# MSB-PCB-1R1.net
KiCad netlist of a schematic drawn in Altium Designer
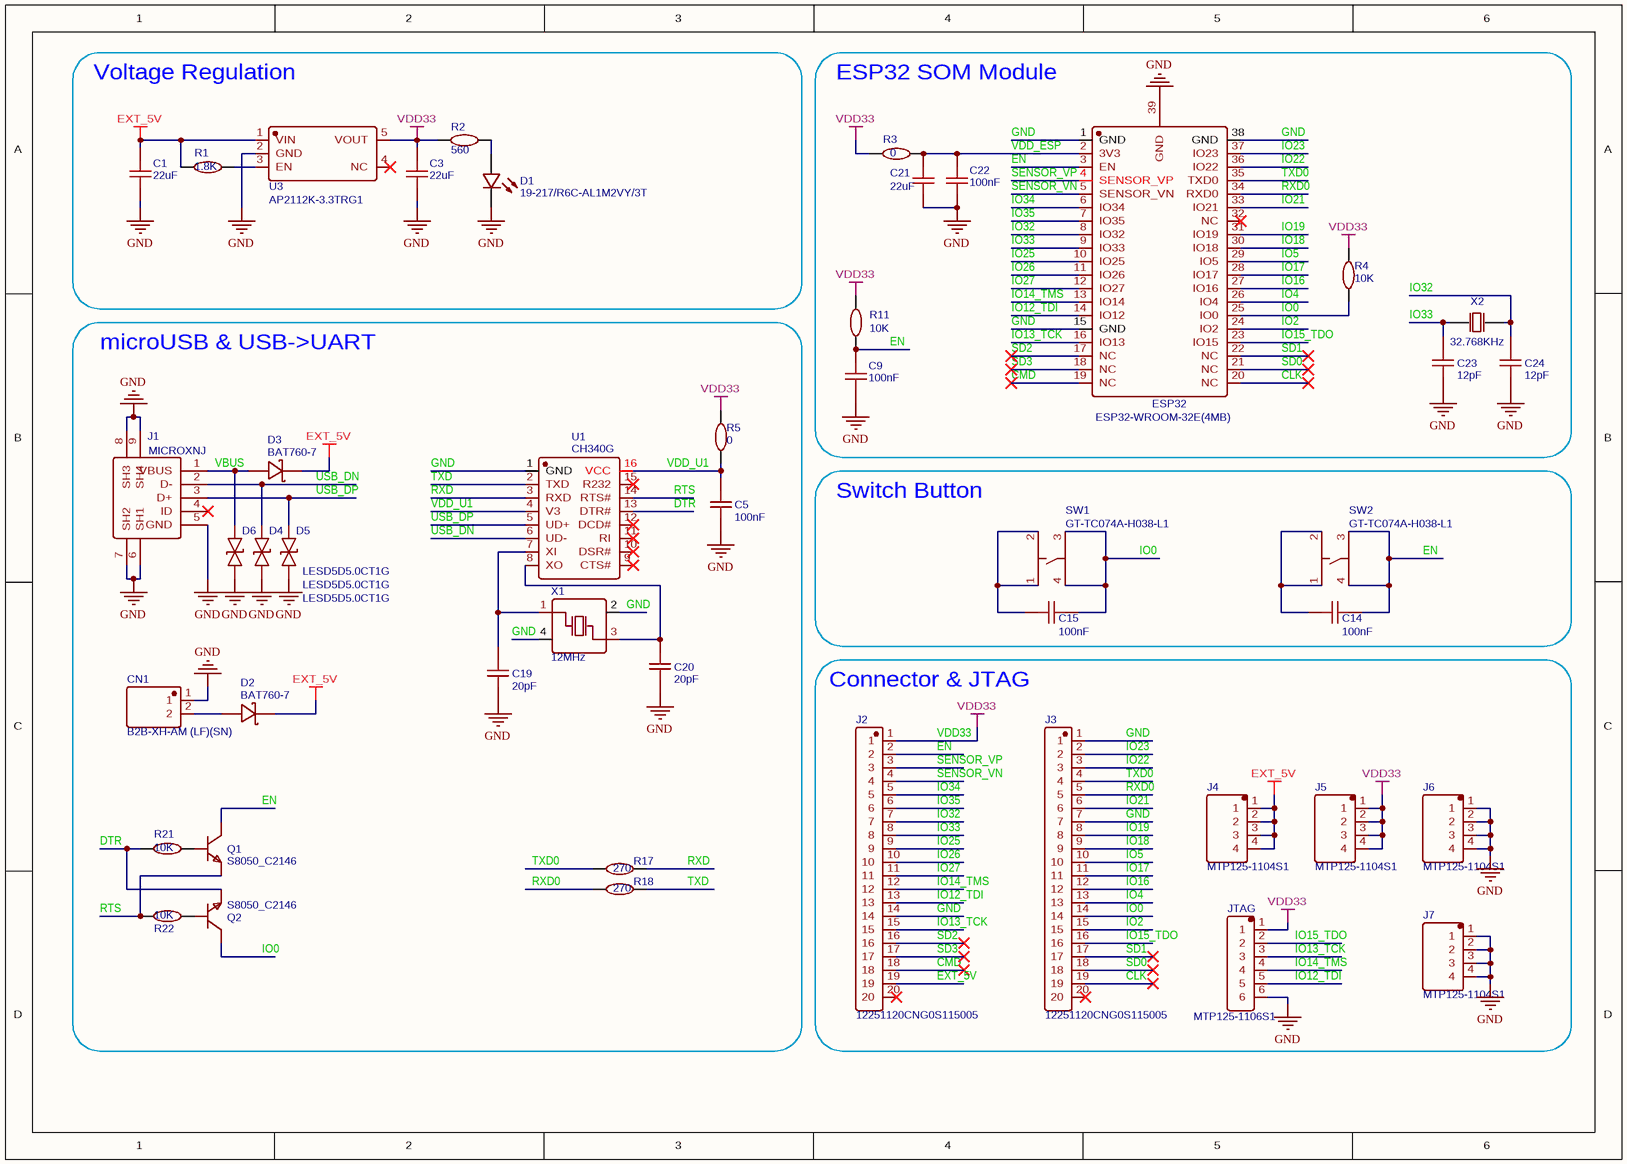
[diagram p0: MSB-PCB-1R1.schdoc]

(export (version "E")
  (design (tool "Eeschema 10.0.6"))
  (components
    (comp (ref "C1")
      (value "22uF")
      (footprint "C0603")
      (fields
        (field (name "BOM_SUPPLIER PART") "C167429")
        (field (name "BOM_MANUFACTURER PART") "GRM188R61A226ME15L")
        (field (name "CONTRIBUTOR") "LCSC")
      )
      (libsource (lib "altium-import") (part "root_1_22uF_"))
    )
    (comp (ref "C3")
      (value "22uF")
      (footprint "C0603")
      (fields
        (field (name "BOM_SUPPLIER PART") "C167429")
        (field (name "BOM_MANUFACTURER PART") "GRM188R61A226ME15L")
        (field (name "CONTRIBUTOR") "LCSC")
      )
      (libsource (lib "altium-import") (part "root_1_22uF_"))
    )
    (comp (ref "C5")
      (value "100nF")
      (footprint "C0603")
      (fields
        (field (name "BOM_MANUFACTURER PART") "CC0603KRX7R9BB104")
        (field (name "BOM_SUPPLIER PART") "C14663")
      )
      (libsource (lib "altium-import") (part "root_3_100nF_"))
    )
    (comp (ref "C9")
      (value "100nF")
      (footprint "C0603")
      (fields
        (field (name "BOM_MANUFACTURER PART") "CC0603KRX7R9BB104")
        (field (name "BOM_SUPPLIER PART") "C14663")
      )
      (libsource (lib "altium-import") (part "root_1_100nF_"))
    )
    (comp (ref "C14")
      (value "100nF")
      (footprint "C0603")
      (fields
        (field (name "BOM_MANUFACTURER PART") "CC0603KRX7R9BB104")
        (field (name "BOM_SUPPLIER PART") "C14663")
      )
      (libsource (lib "altium-import") (part "root_0_100nF_"))
    )
    (comp (ref "C15")
      (value "100nF")
      (footprint "C0603")
      (fields
        (field (name "BOM_MANUFACTURER PART") "CC0603KRX7R9BB104")
        (field (name "BOM_SUPPLIER PART") "C14663")
      )
      (libsource (lib "altium-import") (part "root_0_100nF_"))
    )
    (comp (ref "C19")
      (value "20pF")
      (footprint "C0603")
      (fields
        (field (name "BOM_SUPPLIER PART") "C376774")
        (field (name "BOM_MANUFACTURER PART") "TCC0603COG200J500CT")
        (field (name "CONTRIBUTOR") "LCSC")
      )
      (libsource (lib "altium-import") (part "root_0_20pF_"))
    )
    (comp (ref "C20")
      (value "20pF")
      (footprint "C0603")
      (fields
        (field (name "BOM_SUPPLIER PART") "C376774")
        (field (name "BOM_MANUFACTURER PART") "TCC0603COG200J500CT")
        (field (name "CONTRIBUTOR") "LCSC")
      )
      (libsource (lib "altium-import") (part "root_0_20pF_"))
    )
    (comp (ref "C21")
      (value "22uF")
      (footprint "C0603")
      (fields
        (field (name "BOM_SUPPLIER PART") "C167429")
        (field (name "BOM_MANUFACTURER PART") "GRM188R61A226ME15L")
        (field (name "CONTRIBUTOR") "LCSC")
      )
      (libsource (lib "altium-import") (part "root_1_22uF_"))
    )
    (comp (ref "C22")
      (value "100nF")
      (footprint "C0603")
      (fields
        (field (name "BOM_MANUFACTURER PART") "CC0603KRX7R9BB104")
        (field (name "BOM_SUPPLIER PART") "C14663")
      )
      (libsource (lib "altium-import") (part "root_1_100nF_"))
    )
    (comp (ref "C23")
      (value "12pF")
      (footprint "C0603")
      (fields
        (field (name "BOM_SUPPLIER PART") "C376767")
        (field (name "BOM_MANUFACTURER PART") "TCC0603COG120J500CT")
        (field (name "CONTRIBUTOR") "LCSC")
      )
      (libsource (lib "altium-import") (part "root_0_12pF_"))
    )
    (comp (ref "C24")
      (value "12pF")
      (footprint "C0603")
      (fields
        (field (name "BOM_SUPPLIER PART") "C376767")
        (field (name "BOM_MANUFACTURER PART") "TCC0603COG120J500CT")
        (field (name "CONTRIBUTOR") "LCSC")
      )
      (libsource (lib "altium-import") (part "root_0_12pF_"))
    )
    (comp (ref "CN1")
      (value "B2B-XH-AM (LF)(SN)")
      (footprint "CONN-TH_B2B-XH-AM-LF-SN")
      (fields (field (name "BOM_SUPPLIER PART") "C161869") (field (name "CONTRIBUTOR") "LCSC"))
      (libsource (lib "altium-import") (part "root_0_mirrored_B2B-XH-AM (LF)(SN)_"))
    )
    (comp (ref "D1")
      (value "19-217/R6C-AL1M2VY/3T")
      (footprint "LED0603-R-RD")
      (fields (field (name "BOM_SUPPLIER PART") "C72044"))
      (libsource (lib "altium-import") (part "root_3_19-217/R6C-AL1M2VY/3T_"))
    )
    (comp (ref "D2")
      (value "BAT760-7")
      (footprint "SOD-323_L1.8-W1.3-LS2.5-RD")
      (fields (field (name "BOM_SUPPLIER PART") "C124187") (field (name "CONTRIBUTOR") "LCSC"))
      (libsource (lib "altium-import") (part "root_2_BAT760-7_"))
    )
    (comp (ref "D3")
      (value "BAT760-7")
      (footprint "SOD-323_L1.8-W1.3-LS2.5-RD")
      (fields (field (name "BOM_SUPPLIER PART") "C124187") (field (name "CONTRIBUTOR") "LCSC"))
      (libsource (lib "altium-import") (part "root_2_BAT760-7_"))
    )
    (comp (ref "D4")
      (value "LESD5D5.0CT1G")
      (footprint "SOD-523_L1.2-W0.8-LS1.6-BI")
      (fields (field (name "BOM_SUPPLIER PART") "C383211") (field (name "CONTRIBUTOR") "LCSC"))
      (libsource (lib "altium-import") (part "root_1_LESD5D5.0CT1G_"))
    )
    (comp (ref "D5")
      (value "LESD5D5.0CT1G")
      (footprint "SOD-523_L1.2-W0.8-LS1.6-BI")
      (fields (field (name "BOM_SUPPLIER PART") "C383211") (field (name "CONTRIBUTOR") "LCSC"))
      (libsource (lib "altium-import") (part "root_1_LESD5D5.0CT1G_"))
    )
    (comp (ref "D6")
      (value "LESD5D5.0CT1G")
      (footprint "SOD-523_L1.2-W0.8-LS1.6-BI")
      (fields (field (name "BOM_SUPPLIER PART") "C383211") (field (name "CONTRIBUTOR") "LCSC"))
      (libsource (lib "altium-import") (part "root_1_LESD5D5.0CT1G_"))
    )
    (comp (ref "ESP32")
      (value "ESP32-WROOM-32E(4MB)")
      (footprint "WIFI-SMD_ESP32-WROOM-32E")
      (fields (field (name "BOM_SUPPLIER PART") "C701341") (field (name "CONTRIBUTOR") "LCSC"))
      (libsource (lib "altium-import") (part "root_0_ESP32-WROOM-32E(4MB)_"))
    )
    (comp (ref "J1")
      (value "MICROXNJ")
      (footprint "MICRO-USB-SMD_MICROXNJ")
      (fields
        (field (name "BOM_SUPPLIER PART") "C404969")
        (field (name "BOM_MANUFACTURER PART") "MicroXNJ")
        (field (name "CONTRIBUTOR") "LCSC")
      )
      (libsource (lib "altium-import") (part "root_2_MICROXNJ_"))
    )
    (comp (ref "J2")
      (value "12251120CNG0S115005")
      (footprint "HDR-TH_19P-P2.54-V")
      (fields (field (name "BOM_SUPPLIER PART") "C429964") (field (name "CONTRIBUTOR") "LCSC"))
      (libsource (lib "altium-import") (part "root_0_mirrored_12251120CNG0S115005_"))
    )
    (comp (ref "J3")
      (value "12251120CNG0S115005")
      (footprint "HDR-TH_19P-P2.54-V")
      (fields (field (name "BOM_SUPPLIER PART") "C429964") (field (name "CONTRIBUTOR") "LCSC"))
      (libsource (lib "altium-import") (part "root_0_mirrored_12251120CNG0S115005_"))
    )
    (comp (ref "J4")
      (value "MTP125-1104S1")
      (footprint "HDR-TH_4P-P2.54-V")
      (fields (field (name "BOM_SUPPLIER PART") "C358686") (field (name "CONTRIBUTOR") "LCSC"))
      (libsource (lib "altium-import") (part "root_0_mirrored_MTP125-1104S1_"))
    )
    (comp (ref "J5")
      (value "MTP125-1104S1")
      (footprint "HDR-TH_4P-P2.54-V")
      (fields (field (name "BOM_SUPPLIER PART") "C358686") (field (name "CONTRIBUTOR") "LCSC"))
      (libsource (lib "altium-import") (part "root_0_mirrored_MTP125-1104S1_"))
    )
    (comp (ref "J6")
      (value "MTP125-1104S1")
      (footprint "HDR-TH_4P-P2.54-V")
      (fields (field (name "BOM_SUPPLIER PART") "C358686") (field (name "CONTRIBUTOR") "LCSC"))
      (libsource (lib "altium-import") (part "root_0_mirrored_MTP125-1104S1_"))
    )
    (comp (ref "J7")
      (value "MTP125-1104S1")
      (footprint "HDR-TH_4P-P2.54-V")
      (fields (field (name "BOM_SUPPLIER PART") "C358686") (field (name "CONTRIBUTOR") "LCSC"))
      (libsource (lib "altium-import") (part "root_0_mirrored_MTP125-1104S1_"))
    )
    (comp (ref "JTAG")
      (value "MTP125-1106S1")
      (footprint "HDR-TH_6P-P2.54-V")
      (fields (field (name "BOM_SUPPLIER PART") "C358688") (field (name "CONTRIBUTOR") "LCSC"))
      (libsource (lib "altium-import") (part "root_0_mirrored_MTP125-1106S1_"))
    )
    (comp (ref "Q1")
      (value "S8050_C2146")
      (footprint "SOT-23-3_L3.0-W1.7-P0.95-LS2.9-BR")
      (fields (field (name "BOM_MANUFACTURER PART") "S8050") (field (name "BOM_SUPPLIER PART") "C2146"))
      (libsource (lib "") (part "root_0_S8050_C2146__1"))
    )
    (comp (ref "Q2")
      (value "S8050_C2146")
      (footprint "SOT-23-3_L3.0-W1.7-P0.95-LS2.9-BR")
      (fields (field (name "BOM_MANUFACTURER PART") "S8050") (field (name "BOM_SUPPLIER PART") "C2146"))
      (libsource (lib "altium-import") (part "root_0_S8050_C2146_"))
    )
    (comp (ref "R1")
      (value "1.8K")
      (footprint "R0603")
      (fields
        (field (name "BOM_MANUFACTURER PART") "0603WAJ0182T5E")
        (field (name "BOM_SUPPLIER PART") "C25991")
      )
      (libsource (lib "altium-import") (part "root_0_1.8K_"))
    )
    (comp (ref "R2")
      (value "560")
      (footprint "R0603")
      (fields
        (field (name "BOM_MANUFACTURER PART") "0603WAF5600T5E")
        (field (name "BOM_SUPPLIER PART") "C23204")
      )
      (libsource (lib "altium-import") (part "root_2_560_"))
    )
    (comp (ref "R3")
      (value "0")
      (footprint "R0603")
      (fields
        (field (name "BOM_MANUFACTURER PART") "0603WAF0000T5E")
        (field (name "BOM_SUPPLIER PART") "C21189")
      )
      (libsource (lib "altium-import") (part "root_0_0_"))
    )
    (comp (ref "R4")
      (value "10K")
      (footprint "R0603")
      (fields
        (field (name "BOM_MANUFACTURER PART") "0603WAJ0103T5E")
        (field (name "BOM_SUPPLIER PART") "C15401")
      )
      (libsource (lib "altium-import") (part "root_1_10K_"))
    )
    (comp (ref "R5")
      (value "0")
      (footprint "R0603")
      (fields
        (field (name "BOM_MANUFACTURER PART") "0603WAF0000T5E")
        (field (name "BOM_SUPPLIER PART") "C21189")
      )
      (libsource (lib "altium-import") (part "root_1_0_"))
    )
    (comp (ref "R11")
      (value "10K")
      (footprint "R0603")
      (fields
        (field (name "BOM_MANUFACTURER PART") "0603WAJ0103T5E")
        (field (name "BOM_SUPPLIER PART") "C15401")
      )
      (libsource (lib "altium-import") (part "root_1_10K_"))
    )
    (comp (ref "R17")
      (value "270")
      (footprint "R0603")
      (fields
        (field (name "BOM_MANUFACTURER PART") "0603WAJ0271T5E")
        (field (name "BOM_SUPPLIER PART") "C25223")
      )
      (libsource (lib "altium-import") (part "root_0_270_"))
    )
    (comp (ref "R18")
      (value "270")
      (footprint "R0603")
      (fields
        (field (name "BOM_MANUFACTURER PART") "0603WAJ0271T5E")
        (field (name "BOM_SUPPLIER PART") "C25223")
      )
      (libsource (lib "altium-import") (part "root_0_270_"))
    )
    (comp (ref "R21")
      (value "10K")
      (footprint "R0603")
      (fields
        (field (name "BOM_MANUFACTURER PART") "0603WAJ0103T5E")
        (field (name "BOM_SUPPLIER PART") "C15401")
      )
      (libsource (lib "altium-import") (part "root_0_10K_"))
    )
    (comp (ref "R22")
      (value "10K")
      (footprint "R0603")
      (fields
        (field (name "BOM_MANUFACTURER PART") "0603WAJ0103T5E")
        (field (name "BOM_SUPPLIER PART") "C15401")
      )
      (libsource (lib "altium-import") (part "root_0_10K_"))
    )
    (comp (ref "SW1")
      (value "GT-TC074A-H038-L1")
      (footprint "SW-SMD_4P-L4.5-W4.5-P3.00-LS7.0")
      (fields (field (name "BOM_SUPPLIER PART") "C843603") (field (name "CONTRIBUTOR") "LCSC"))
      (libsource (lib "altium-import") (part "root_1_GT-TC074A-H038-L1_"))
    )
    (comp (ref "SW2")
      (value "GT-TC074A-H038-L1")
      (footprint "SW-SMD_4P-L4.5-W4.5-P3.00-LS7.0")
      (fields (field (name "BOM_SUPPLIER PART") "C843603") (field (name "CONTRIBUTOR") "LCSC"))
      (libsource (lib "altium-import") (part "root_1_GT-TC074A-H038-L1_"))
    )
    (comp (ref "U1")
      (value "CH340G")
      (footprint "SOIC-16_L9.9-W3.9-P1.27-LS6.0-TL")
      (fields (field (name "BOM_SUPPLIER PART") "C14267"))
      (libsource (lib "altium-import") (part "root_0_CH340G_"))
    )
    (comp (ref "U3")
      (value "AP2112K-3.3TRG1")
      (footprint "SOT-25-5_L3.0-W1.8-P0.95-LS3.0-BR")
      (fields (field (name "BOM_SUPPLIER PART") "C51118") (field (name "CONTRIBUTOR") "LCSC"))
      (libsource (lib "altium-import") (part "root_0_AP2112K-3.3TRG1_"))
    )
    (comp (ref "X1")
      (value "12MHz")
      (footprint "OSC-SMD_4P-L3.2-W2.5-BL")
      (fields
        (field (name "BOM_MANUFACTURER PART") "X322512MSB4SI")
        (field (name "BOM_SUPPLIER PART") "C9002")
      )
      (libsource (lib "altium-import") (part "root_2_12MHz_"))
    )
    (comp (ref "X2")
      (value "32.768KHz")
      (footprint "OSC-SMD_L3.2-W1.5")
      (fields
        (field (name "BOM_SUPPLIER PART") "C271654")
        (field (name "BOM_MANUFACTURER PART") "SF32K32768D31T-12.5")
        (field (name "CONTRIBUTOR") "LCSC")
      )
      (libsource (lib "altium-import") (part "root_0_32.768KHz_"))
    )
  )
  (nets
    (net (code "1") (name "/CLK") (class "Default")
      (node (ref "ESP32") (pin "20") (pinfunction "NC_20") (pintype "passive"))
      (node (ref "J3") (pin "19") (pinfunction "19_19") (pintype "passive"))
    )
    (net (code "2") (name "/CMD") (class "Default")
      (node (ref "ESP32") (pin "19") (pinfunction "NC_19") (pintype "passive"))
      (node (ref "J2") (pin "18") (pinfunction "18_18") (pintype "passive"))
    )
    (net (code "3") (name "/DTR") (class "Default")
      (node (ref "Q2") (pin "2") (pinfunction "E_2") (pintype "passive"))
      (node (ref "R21") (pin "1") (pinfunction "1_1") (pintype "passive"))
      (node (ref "U1") (pin "13") (pinfunction "DTR#_13") (pintype "passive"))
    )
    (net (code "4") (name "/EN") (class "Default")
      (node (ref "C14") (pin "2") (pinfunction "2_2") (pintype "passive"))
      (node (ref "C9") (pin "2") (pinfunction "2_2") (pintype "passive"))
      (node (ref "ESP32") (pin "3") (pinfunction "EN_3") (pintype "passive"))
      (node (ref "J2") (pin "2") (pinfunction "2_2") (pintype "passive"))
      (node (ref "Q1") (pin "3") (pinfunction "C_3") (pintype "passive"))
      (node (ref "R11") (pin "1") (pinfunction "1_1") (pintype "passive"))
      (node (ref "SW2") (pin "3") (pinfunction "3_3") (pintype "passive"))
      (node (ref "SW2") (pin "4") (pinfunction "4_4") (pintype "passive"))
    )
    (net (code "5") (name "/IO0") (class "Default")
      (node (ref "C15") (pin "2") (pinfunction "2_2") (pintype "passive"))
      (node (ref "ESP32") (pin "25") (pinfunction "IO0_25") (pintype "passive"))
      (node (ref "J3") (pin "14") (pinfunction "14_14") (pintype "passive"))
      (node (ref "Q2") (pin "3") (pinfunction "C_3") (pintype "passive"))
      (node (ref "R4") (pin "1") (pinfunction "1_1") (pintype "passive"))
      (node (ref "SW1") (pin "3") (pinfunction "3_3") (pintype "passive"))
      (node (ref "SW1") (pin "4") (pinfunction "4_4") (pintype "passive"))
    )
    (net (code "6") (name "/IO2") (class "Default")
      (node (ref "ESP32") (pin "24") (pinfunction "IO2_24") (pintype "passive"))
      (node (ref "J3") (pin "15") (pinfunction "15_15") (pintype "passive"))
    )
    (net (code "7") (name "/IO4") (class "Default")
      (node (ref "ESP32") (pin "26") (pinfunction "IO4_26") (pintype "passive"))
      (node (ref "J3") (pin "13") (pinfunction "13_13") (pintype "passive"))
    )
    (net (code "8") (name "/IO5") (class "Default")
      (node (ref "ESP32") (pin "29") (pinfunction "IO5_29") (pintype "passive"))
      (node (ref "J3") (pin "10") (pinfunction "10_10") (pintype "passive"))
    )
    (net (code "9") (name "/IO12_TDI") (class "Default")
      (node (ref "ESP32") (pin "14") (pinfunction "IO12_14") (pintype "passive"))
      (node (ref "J2") (pin "13") (pinfunction "13_13") (pintype "passive"))
      (node (ref "JTAG") (pin "5") (pinfunction "5_5") (pintype "passive"))
    )
    (net (code "10") (name "/IO13_TCK") (class "Default")
      (node (ref "ESP32") (pin "16") (pinfunction "IO13_16") (pintype "passive"))
      (node (ref "J2") (pin "15") (pinfunction "15_15") (pintype "passive"))
      (node (ref "JTAG") (pin "3") (pinfunction "3_3") (pintype "passive"))
    )
    (net (code "11") (name "/IO14_TMS") (class "Default")
      (node (ref "ESP32") (pin "13") (pinfunction "IO14_13") (pintype "passive"))
      (node (ref "J2") (pin "12") (pinfunction "12_12") (pintype "passive"))
      (node (ref "JTAG") (pin "4") (pinfunction "4_4") (pintype "passive"))
    )
    (net (code "12") (name "/IO15_TDO") (class "Default")
      (node (ref "ESP32") (pin "23") (pinfunction "IO15_23") (pintype "passive"))
      (node (ref "J3") (pin "16") (pinfunction "16_16") (pintype "passive"))
      (node (ref "JTAG") (pin "2") (pinfunction "2_2") (pintype "passive"))
    )
    (net (code "13") (name "/IO16") (class "Default")
      (node (ref "ESP32") (pin "27") (pinfunction "IO16_27") (pintype "passive"))
      (node (ref "J3") (pin "12") (pinfunction "12_12") (pintype "passive"))
    )
    (net (code "14") (name "/IO17") (class "Default")
      (node (ref "ESP32") (pin "28") (pinfunction "IO17_28") (pintype "passive"))
      (node (ref "J3") (pin "11") (pinfunction "11_11") (pintype "passive"))
    )
    (net (code "15") (name "/IO18") (class "Default")
      (node (ref "ESP32") (pin "30") (pinfunction "IO18_30") (pintype "passive"))
      (node (ref "J3") (pin "9") (pinfunction "9_9") (pintype "passive"))
    )
    (net (code "16") (name "/IO19") (class "Default")
      (node (ref "ESP32") (pin "31") (pinfunction "IO19_31") (pintype "passive"))
      (node (ref "J3") (pin "8") (pinfunction "8_8") (pintype "passive"))
    )
    (net (code "17") (name "/IO21") (class "Default")
      (node (ref "ESP32") (pin "33") (pinfunction "IO21_33") (pintype "passive"))
      (node (ref "J3") (pin "6") (pinfunction "6_6") (pintype "passive"))
    )
    (net (code "18") (name "/IO22") (class "Default")
      (node (ref "ESP32") (pin "36") (pinfunction "IO22_36") (pintype "passive"))
      (node (ref "J3") (pin "3") (pinfunction "3_3") (pintype "passive"))
    )
    (net (code "19") (name "/IO23") (class "Default")
      (node (ref "ESP32") (pin "37") (pinfunction "IO23_37") (pintype "passive"))
      (node (ref "J3") (pin "2") (pinfunction "2_2") (pintype "passive"))
    )
    (net (code "20") (name "/IO25") (class "Default")
      (node (ref "ESP32") (pin "10") (pinfunction "IO25_10") (pintype "passive"))
      (node (ref "J2") (pin "9") (pinfunction "9_9") (pintype "passive"))
    )
    (net (code "21") (name "/IO26") (class "Default")
      (node (ref "ESP32") (pin "11") (pinfunction "IO26_11") (pintype "passive"))
      (node (ref "J2") (pin "10") (pinfunction "10_10") (pintype "passive"))
    )
    (net (code "22") (name "/IO27") (class "Default")
      (node (ref "ESP32") (pin "12") (pinfunction "IO27_12") (pintype "passive"))
      (node (ref "J2") (pin "11") (pinfunction "11_11") (pintype "passive"))
    )
    (net (code "23") (name "/IO32") (class "Default")
      (node (ref "C24") (pin "2") (pinfunction "2_2") (pintype "passive"))
      (node (ref "ESP32") (pin "8") (pinfunction "IO32_8") (pintype "passive"))
      (node (ref "J2") (pin "7") (pinfunction "7_7") (pintype "passive"))
      (node (ref "X2") (pin "2") (pinfunction "OSC2_2") (pintype "passive"))
    )
    (net (code "24") (name "/IO33") (class "Default")
      (node (ref "C23") (pin "2") (pinfunction "2_2") (pintype "passive"))
      (node (ref "ESP32") (pin "9") (pinfunction "IO33_9") (pintype "passive"))
      (node (ref "J2") (pin "8") (pinfunction "8_8") (pintype "passive"))
      (node (ref "X2") (pin "1") (pinfunction "OSC1_1") (pintype "passive"))
    )
    (net (code "25") (name "/IO34") (class "Default")
      (node (ref "ESP32") (pin "6") (pinfunction "IO34_6") (pintype "passive"))
      (node (ref "J2") (pin "5") (pinfunction "5_5") (pintype "passive"))
    )
    (net (code "26") (name "/IO35") (class "Default")
      (node (ref "ESP32") (pin "7") (pinfunction "IO35_7") (pintype "passive"))
      (node (ref "J2") (pin "6") (pinfunction "6_6") (pintype "passive"))
    )
    (net (code "27") (name "/RTS") (class "Default")
      (node (ref "Q1") (pin "2") (pinfunction "E_2") (pintype "passive"))
      (node (ref "R22") (pin "1") (pinfunction "1_1") (pintype "passive"))
      (node (ref "U1") (pin "14") (pinfunction "RTS#_14") (pintype "passive"))
    )
    (net (code "28") (name "/RXD") (class "Default")
      (node (ref "R17") (pin "2") (pinfunction "2_2") (pintype "passive"))
      (node (ref "U1") (pin "3") (pinfunction "RXD_3") (pintype "passive"))
    )
    (net (code "29") (name "/RXD0") (class "Default")
      (node (ref "ESP32") (pin "34") (pinfunction "RXD0_34") (pintype "passive"))
      (node (ref "J3") (pin "5") (pinfunction "5_5") (pintype "passive"))
      (node (ref "R18") (pin "1") (pinfunction "1_1") (pintype "passive"))
    )
    (net (code "30") (name "/SD0") (class "Default")
      (node (ref "ESP32") (pin "21") (pinfunction "NC_21") (pintype "passive"))
      (node (ref "J3") (pin "18") (pinfunction "18_18") (pintype "passive"))
    )
    (net (code "31") (name "/SD1") (class "Default")
      (node (ref "ESP32") (pin "22") (pinfunction "NC_22") (pintype "passive"))
      (node (ref "J3") (pin "17") (pinfunction "17_17") (pintype "passive"))
    )
    (net (code "32") (name "/SD2") (class "Default")
      (node (ref "ESP32") (pin "17") (pinfunction "NC_17") (pintype "passive"))
      (node (ref "J2") (pin "16") (pinfunction "16_16") (pintype "passive"))
    )
    (net (code "33") (name "/SD3") (class "Default")
      (node (ref "ESP32") (pin "18") (pinfunction "NC_18") (pintype "passive"))
      (node (ref "J2") (pin "17") (pinfunction "17_17") (pintype "passive"))
    )
    (net (code "34") (name "/SENSOR_VN") (class "Default")
      (node (ref "ESP32") (pin "5") (pinfunction "SENSOR_VN_5") (pintype "passive"))
      (node (ref "J2") (pin "4") (pinfunction "4_4") (pintype "passive"))
    )
    (net (code "35") (name "/SENSOR_VP") (class "Default")
      (node (ref "ESP32") (pin "4") (pinfunction "SENSOR_VP_4") (pintype "passive"))
      (node (ref "J2") (pin "3") (pinfunction "3_3") (pintype "passive"))
    )
    (net (code "36") (name "/TXD") (class "Default")
      (node (ref "R18") (pin "2") (pinfunction "2_2") (pintype "passive"))
      (node (ref "U1") (pin "2") (pinfunction "TXD_2") (pintype "passive"))
    )
    (net (code "37") (name "/TXD0") (class "Default")
      (node (ref "ESP32") (pin "35") (pinfunction "TXD0_35") (pintype "passive"))
      (node (ref "J3") (pin "4") (pinfunction "4_4") (pintype "passive"))
      (node (ref "R17") (pin "1") (pinfunction "1_1") (pintype "passive"))
    )
    (net (code "38") (name "/USB_DN") (class "Default")
      (node (ref "D4") (pin "2") (pinfunction "2_2") (pintype "passive"))
      (node (ref "J1") (pin "2") (pinfunction "D-_2") (pintype "passive"))
      (node (ref "U1") (pin "6") (pinfunction "UD-_6") (pintype "passive"))
    )
    (net (code "39") (name "/USB_DP") (class "Default")
      (node (ref "D5") (pin "2") (pinfunction "2_2") (pintype "passive"))
      (node (ref "J1") (pin "3") (pinfunction "D+_3") (pintype "passive"))
      (node (ref "U1") (pin "5") (pinfunction "UD+_5") (pintype "passive"))
    )
    (net (code "40") (name "/VBUS") (class "Default")
      (node (ref "D3") (pin "2") (pinfunction "2_2") (pintype "passive"))
      (node (ref "D6") (pin "2") (pinfunction "2_2") (pintype "passive"))
      (node (ref "J1") (pin "1") (pinfunction "VBUS_1") (pintype "passive"))
    )
    (net (code "41") (name "/VDD_ESP") (class "Default")
      (node (ref "C21") (pin "2") (pinfunction "2_2") (pintype "passive"))
      (node (ref "C22") (pin "2") (pinfunction "2_2") (pintype "passive"))
      (node (ref "ESP32") (pin "2") (pinfunction "3V3_2") (pintype "passive"))
      (node (ref "R3") (pin "2") (pinfunction "2_2") (pintype "passive"))
    )
    (net (code "42") (name "/VDD_U1") (class "Default")
      (node (ref "C5") (pin "1") (pinfunction "1_1") (pintype "passive"))
      (node (ref "R5") (pin "1") (pinfunction "1_1") (pintype "passive"))
      (node (ref "U1") (pin "16") (pinfunction "VCC_16") (pintype "passive"))
      (node (ref "U1") (pin "4") (pinfunction "V3_4") (pintype "passive"))
    )
    (net (code "43") (name "EXT_5V") (class "Default")
      (node (ref "C1") (pin "2") (pinfunction "2_2") (pintype "passive"))
      (node (ref "D2") (pin "1") (pinfunction "1_1") (pintype "passive"))
      (node (ref "D3") (pin "1") (pinfunction "1_1") (pintype "passive"))
      (node (ref "J2") (pin "19") (pinfunction "19_19") (pintype "passive"))
      (node (ref "J4") (pin "1") (pinfunction "1_1") (pintype "passive"))
      (node (ref "J4") (pin "2") (pinfunction "2_2") (pintype "passive"))
      (node (ref "J4") (pin "3") (pinfunction "3_3") (pintype "passive"))
      (node (ref "J4") (pin "4") (pinfunction "4_4") (pintype "passive"))
      (node (ref "R1") (pin "1") (pinfunction "1_1") (pintype "passive"))
      (node (ref "U3") (pin "1") (pinfunction "VIN_1") (pintype "passive"))
    )
    (net (code "44") (name "GND") (class "Default")
      (node (ref "C1") (pin "1") (pinfunction "1_1") (pintype "passive"))
      (node (ref "C19") (pin "1") (pinfunction "1_1") (pintype "passive"))
      (node (ref "C20") (pin "1") (pinfunction "1_1") (pintype "passive"))
      (node (ref "C21") (pin "1") (pinfunction "1_1") (pintype "passive"))
      (node (ref "C22") (pin "1") (pinfunction "1_1") (pintype "passive"))
      (node (ref "C23") (pin "1") (pinfunction "1_1") (pintype "passive"))
      (node (ref "C24") (pin "1") (pinfunction "1_1") (pintype "passive"))
      (node (ref "C3") (pin "1") (pinfunction "1_1") (pintype "passive"))
      (node (ref "C5") (pin "2") (pinfunction "2_2") (pintype "passive"))
      (node (ref "C9") (pin "1") (pinfunction "1_1") (pintype "passive"))
      (node (ref "CN1") (pin "1") (pinfunction "1_1") (pintype "passive"))
      (node (ref "D1") (pin "2") (pinfunction "C_2") (pintype "passive"))
      (node (ref "D4") (pin "1") (pinfunction "1_1") (pintype "passive"))
      (node (ref "D5") (pin "1") (pinfunction "1_1") (pintype "passive"))
      (node (ref "D6") (pin "1") (pinfunction "1_1") (pintype "passive"))
      (node (ref "ESP32") (pin "1") (pinfunction "GND_1") (pintype "passive"))
      (node (ref "ESP32") (pin "15") (pinfunction "GND_15") (pintype "passive"))
      (node (ref "ESP32") (pin "38") (pinfunction "GND_38") (pintype "passive"))
      (node (ref "ESP32") (pin "39") (pinfunction "GND_39") (pintype "passive"))
      (node (ref "J1") (pin "5") (pinfunction "GND_5") (pintype "passive"))
      (node (ref "J1") (pin "6") (pinfunction "SH1_6") (pintype "passive"))
      (node (ref "J1") (pin "7") (pinfunction "SH2_7") (pintype "passive"))
      (node (ref "J1") (pin "8") (pinfunction "SH3_8") (pintype "passive"))
      (node (ref "J1") (pin "9") (pinfunction "SH4_9") (pintype "passive"))
      (node (ref "J2") (pin "14") (pinfunction "14_14") (pintype "passive"))
      (node (ref "J3") (pin "1") (pinfunction "1_1") (pintype "passive"))
      (node (ref "J3") (pin "7") (pinfunction "7_7") (pintype "passive"))
      (node (ref "J6") (pin "1") (pinfunction "1_1") (pintype "passive"))
      (node (ref "J6") (pin "2") (pinfunction "2_2") (pintype "passive"))
      (node (ref "J6") (pin "3") (pinfunction "3_3") (pintype "passive"))
      (node (ref "J6") (pin "4") (pinfunction "4_4") (pintype "passive"))
      (node (ref "J7") (pin "1") (pinfunction "1_1") (pintype "passive"))
      (node (ref "J7") (pin "2") (pinfunction "2_2") (pintype "passive"))
      (node (ref "J7") (pin "3") (pinfunction "3_3") (pintype "passive"))
      (node (ref "J7") (pin "4") (pinfunction "4_4") (pintype "passive"))
      (node (ref "JTAG") (pin "6") (pinfunction "6_6") (pintype "passive"))
      (node (ref "U1") (pin "1") (pinfunction "GND_1") (pintype "passive"))
      (node (ref "U3") (pin "2") (pinfunction "GND_2") (pintype "passive"))
      (node (ref "X1") (pin "2") (pinfunction "GND_2") (pintype "passive"))
      (node (ref "X1") (pin "4") (pinfunction "GND_4") (pintype "passive"))
    )
    (net (code "45") (name "Net-(C14-Pad1)") (class "Default")
      (node (ref "C14") (pin "1") (pinfunction "1_1") (pintype "passive"))
      (node (ref "SW2") (pin "1") (pinfunction "1_1") (pintype "passive"))
      (node (ref "SW2") (pin "2") (pinfunction "2_2") (pintype "passive"))
    )
    (net (code "46") (name "Net-(C15-Pad1)") (class "Default")
      (node (ref "C15") (pin "1") (pinfunction "1_1") (pintype "passive"))
      (node (ref "SW1") (pin "1") (pinfunction "1_1") (pintype "passive"))
      (node (ref "SW1") (pin "2") (pinfunction "2_2") (pintype "passive"))
    )
    (net (code "47") (name "Net-(CN1-Pad2)") (class "Default")
      (node (ref "CN1") (pin "2") (pinfunction "2_2") (pintype "passive"))
      (node (ref "D2") (pin "2") (pinfunction "2_2") (pintype "passive"))
    )
    (net (code "48") (name "Net-(D1-A)") (class "Default")
      (node (ref "D1") (pin "1") (pinfunction "A_1") (pintype "passive"))
      (node (ref "R2") (pin "1") (pinfunction "1_1") (pintype "passive"))
    )
    (net (code "49") (name "Net-(Q1-B)") (class "Default")
      (node (ref "Q1") (pin "1") (pinfunction "B_1") (pintype "passive"))
      (node (ref "R21") (pin "2") (pinfunction "2_2") (pintype "passive"))
    )
    (net (code "50") (name "Net-(Q2-B)") (class "Default")
      (node (ref "Q2") (pin "1") (pinfunction "B_1") (pintype "passive"))
      (node (ref "R22") (pin "2") (pinfunction "2_2") (pintype "passive"))
    )
    (net (code "51") (name "Net-(U1-XI)") (class "Default")
      (node (ref "C19") (pin "2") (pinfunction "2_2") (pintype "passive"))
      (node (ref "U1") (pin "7") (pinfunction "XI_7") (pintype "passive"))
      (node (ref "X1") (pin "1") (pinfunction "OSC1_1") (pintype "passive"))
    )
    (net (code "52") (name "Net-(U1-XO)") (class "Default")
      (node (ref "C20") (pin "2") (pinfunction "2_2") (pintype "passive"))
      (node (ref "U1") (pin "8") (pinfunction "XO_8") (pintype "passive"))
      (node (ref "X1") (pin "3") (pinfunction "OSC2_3") (pintype "passive"))
    )
    (net (code "53") (name "Net-(U3-EN)") (class "Default")
      (node (ref "R1") (pin "2") (pinfunction "2_2") (pintype "passive"))
      (node (ref "U3") (pin "3") (pinfunction "EN_3") (pintype "passive"))
    )
    (net (code "54") (name "VDD33") (class "Default")
      (node (ref "C3") (pin "2") (pinfunction "2_2") (pintype "passive"))
      (node (ref "J2") (pin "1") (pinfunction "1_1") (pintype "passive"))
      (node (ref "J5") (pin "1") (pinfunction "1_1") (pintype "passive"))
      (node (ref "J5") (pin "2") (pinfunction "2_2") (pintype "passive"))
      (node (ref "J5") (pin "3") (pinfunction "3_3") (pintype "passive"))
      (node (ref "J5") (pin "4") (pinfunction "4_4") (pintype "passive"))
      (node (ref "JTAG") (pin "1") (pinfunction "1_1") (pintype "passive"))
      (node (ref "R11") (pin "2") (pinfunction "2_2") (pintype "passive"))
      (node (ref "R2") (pin "2") (pinfunction "2_2") (pintype "passive"))
      (node (ref "R3") (pin "1") (pinfunction "1_1") (pintype "passive"))
      (node (ref "R4") (pin "2") (pinfunction "2_2") (pintype "passive"))
      (node (ref "R5") (pin "2") (pinfunction "2_2") (pintype "passive"))
      (node (ref "U3") (pin "5") (pinfunction "VOUT_5") (pintype "passive"))
    )
    (net (code "55") (name "unconnected-(ESP32-NC-Pad32)") (class "Default")
      (node (ref "ESP32") (pin "32") (pinfunction "NC_32") (pintype "passive+no_connect"))
    )
    (net (code "56") (name "unconnected-(J1-ID-Pad4)") (class "Default")
      (node (ref "J1") (pin "4") (pinfunction "ID_4") (pintype "passive+no_connect"))
    )
    (net (code "57") (name "unconnected-(J2-Pad20)") (class "Default")
      (node (ref "J2") (pin "20") (pinfunction "20_20") (pintype "passive+no_connect"))
    )
    (net (code "58") (name "unconnected-(J3-Pad20)") (class "Default")
      (node (ref "J3") (pin "20") (pinfunction "20_20") (pintype "passive+no_connect"))
    )
    (net (code "59") (name "unconnected-(U1-CTS#-Pad9)") (class "Default")
      (node (ref "U1") (pin "9") (pinfunction "CTS#_9") (pintype "passive+no_connect"))
    )
    (net (code "60") (name "unconnected-(U1-DCD#-Pad12)") (class "Default")
      (node (ref "U1") (pin "12") (pinfunction "DCD#_12") (pintype "passive+no_connect"))
    )
    (net (code "61") (name "unconnected-(U1-DSR#-Pad10)") (class "Default")
      (node (ref "U1") (pin "10") (pinfunction "DSR#_10") (pintype "passive+no_connect"))
    )
    (net (code "62") (name "unconnected-(U1-R232-Pad15)") (class "Default")
      (node (ref "U1") (pin "15") (pinfunction "R232_15") (pintype "passive+no_connect"))
    )
    (net (code "63") (name "unconnected-(U1-RI-Pad11)") (class "Default")
      (node (ref "U1") (pin "11") (pinfunction "RI_11") (pintype "passive+no_connect"))
    )
    (net (code "64") (name "unconnected-(U3-NC-Pad4)") (class "Default")
      (node (ref "U3") (pin "4") (pinfunction "NC_4") (pintype "passive+no_connect"))
    )
  )
)
